# bue_steuerung_3.net
KiCad netlist of a schematic drawn in EAGLE
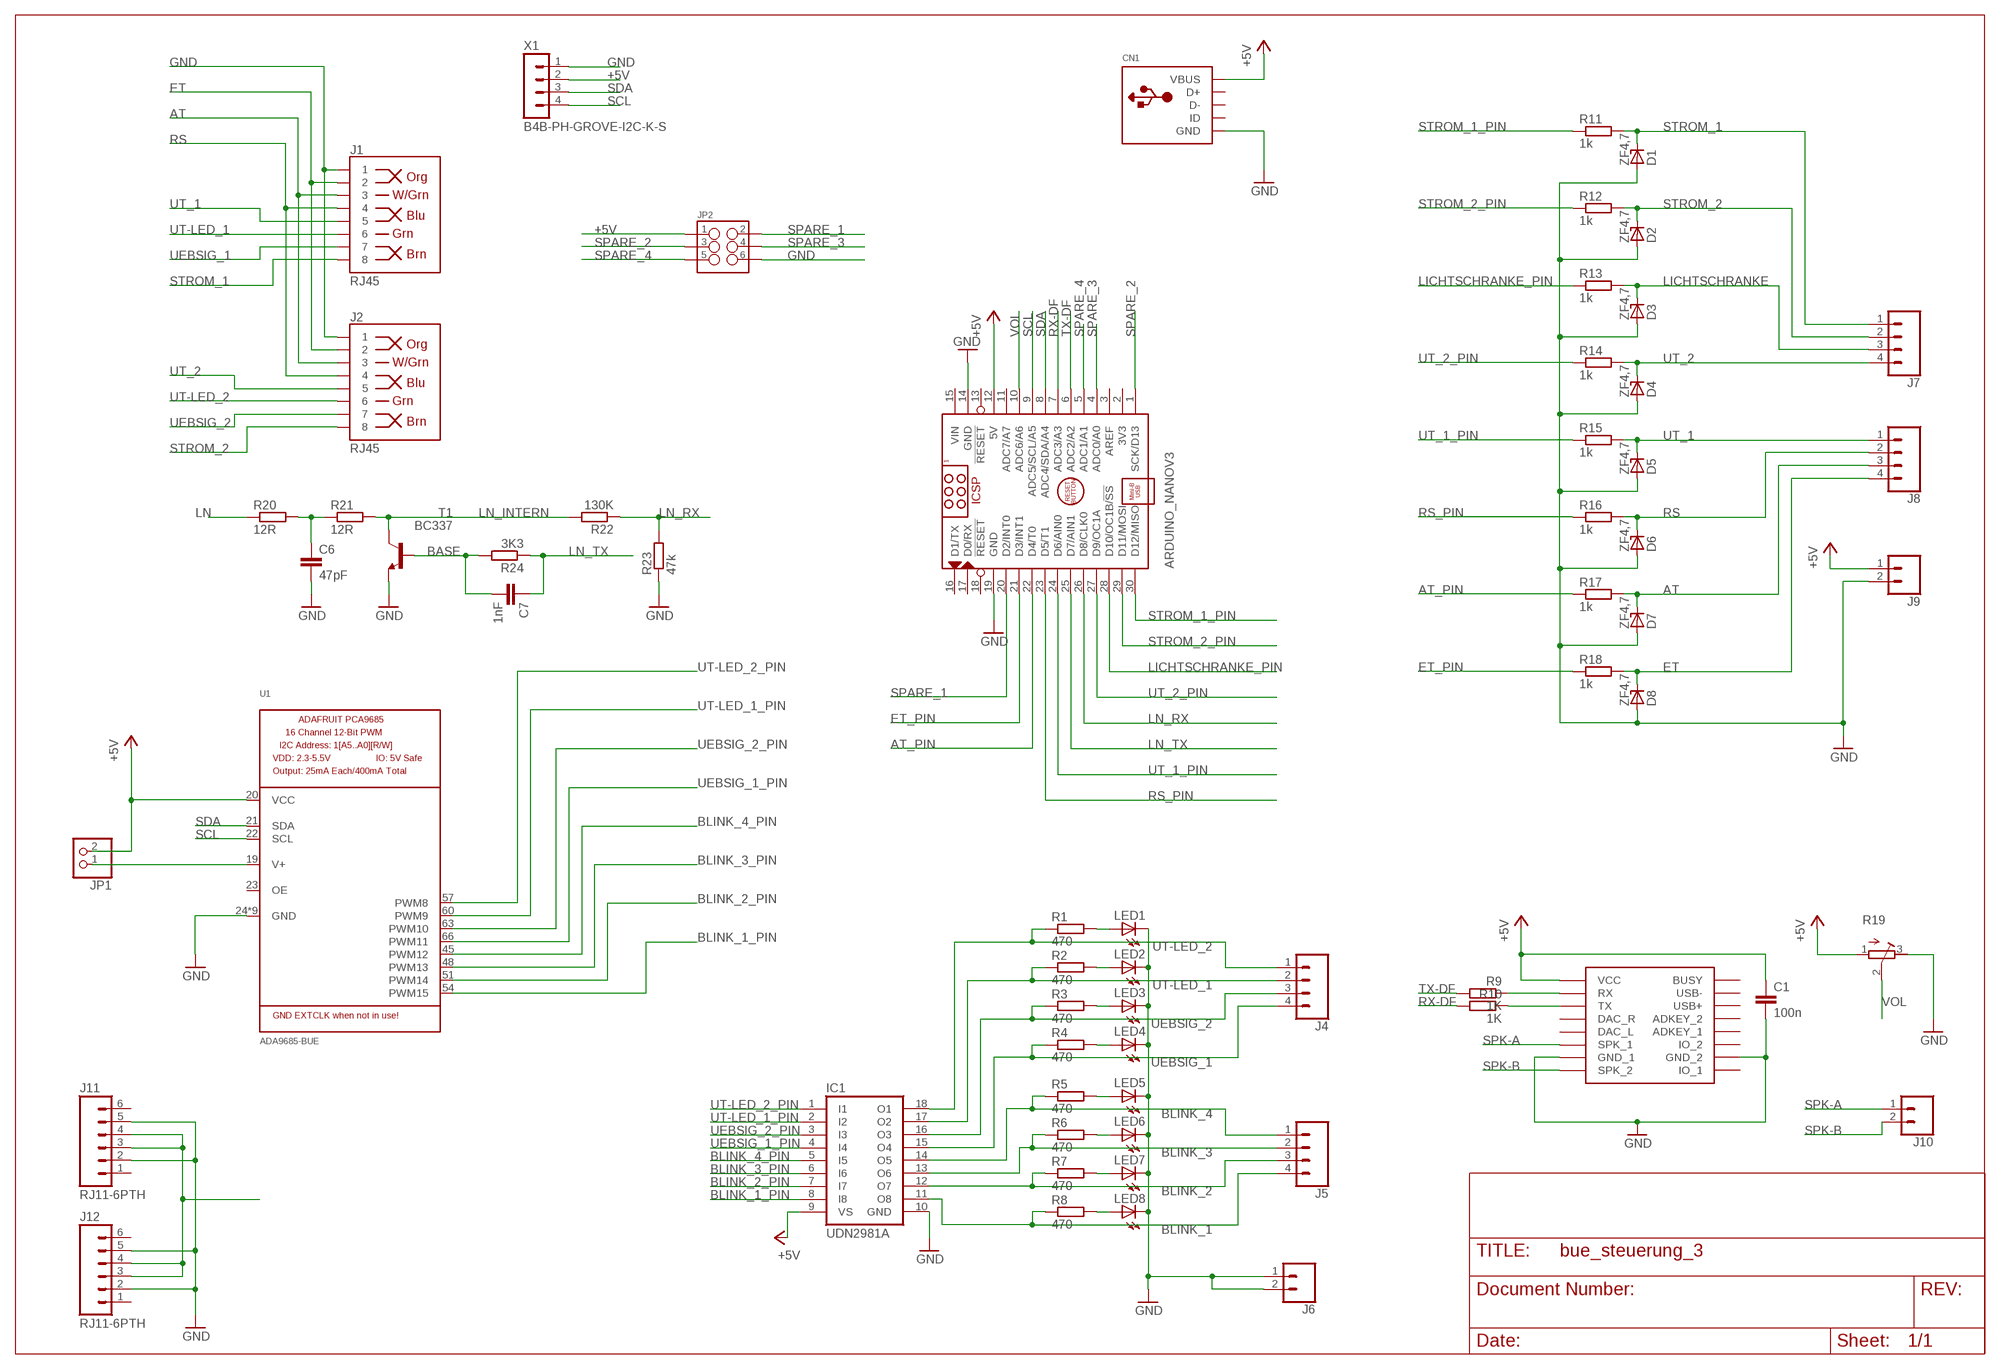
[diagram p0: schematic, sheet 1]

(export (version "E")
  (design (tool "Eeschema 10.0.6"))
  (components
    (comp (ref "ARDUINO_NANOV3")
      (value "ARDUINO_NANO")
      (footprint "eagle-import:ARDUINO_NANO")
      (libsource (lib "eagle-import") (part "ARDUINO_NANO"))
    )
    (comp (ref "C1")
      (value "100n")
      (footprint "eagle-import:C0805")
      (libsource (lib "eagle-import") (part "C-EUC0805"))
    )
    (comp (ref "C6")
      (value "47pF")
      (footprint "eagle-import:C025-024X044")
      (libsource (lib "eagle-import") (part "C-EU025-024X044"))
    )
    (comp (ref "C7")
      (value "1nF")
      (footprint "eagle-import:C025-025X050")
      (libsource (lib "eagle-import") (part "C-EU025-025X050"))
    )
    (comp (ref "CN1")
      (value "USBMOLEX")
      (footprint "eagle-import:USB-MINIB-THM-MOLEX")
      (libsource (lib "eagle-import") (part "USBMOLEX"))
    )
    (comp (ref "D1")
      (value "ZF4,7")
      (footprint "eagle-import:ZDIO-7.5")
      (libsource (lib "eagle-import") (part "ZENER-DIODEZD-7.5"))
    )
    (comp (ref "D2")
      (value "ZF4,7")
      (footprint "eagle-import:ZDIO-7.5")
      (libsource (lib "eagle-import") (part "ZENER-DIODEZD-7.5"))
    )
    (comp (ref "D3")
      (value "ZF4,7")
      (footprint "eagle-import:ZDIO-7.5")
      (libsource (lib "eagle-import") (part "ZENER-DIODEZD-7.5"))
    )
    (comp (ref "D4")
      (value "ZF4,7")
      (footprint "eagle-import:ZDIO-7.5")
      (libsource (lib "eagle-import") (part "ZENER-DIODEZD-7.5"))
    )
    (comp (ref "D5")
      (value "ZF4,7")
      (footprint "eagle-import:ZDIO-7.5")
      (libsource (lib "eagle-import") (part "ZENER-DIODEZD-7.5"))
    )
    (comp (ref "D6")
      (value "ZF4,7")
      (footprint "eagle-import:ZDIO-7.5")
      (libsource (lib "eagle-import") (part "ZENER-DIODEZD-7.5"))
    )
    (comp (ref "D7")
      (value "ZF4,7")
      (footprint "eagle-import:ZDIO-7.5")
      (libsource (lib "eagle-import") (part "ZENER-DIODEZD-7.5"))
    )
    (comp (ref "D8")
      (value "ZF4,7")
      (footprint "eagle-import:ZDIO-7.5")
      (libsource (lib "eagle-import") (part "ZENER-DIODEZD-7.5"))
    )
    (comp (ref "IC1")
      (value "UDN2981A")
      (footprint "eagle-import:DIL18")
      (libsource (lib "eagle-import") (part "UDN298A1"))
    )
    (comp (ref "J1")
      (value "RJ45")
      (footprint "eagle-import:RJ45-8")
      (libsource (lib "eagle-import") (part "RJ45-8"))
    )
    (comp (ref "J2")
      (value "RJ45")
      (footprint "eagle-import:RJ45-8")
      (libsource (lib "eagle-import") (part "RJ45-8"))
    )
    (comp (ref "J4")
      (value "CONN_04SCREW")
      (footprint "eagle-import:SCREWTERMINAL-3.5MM-4")
      (libsource (lib "eagle-import") (part "CONN_04SCREW"))
    )
    (comp (ref "J5")
      (value "CONN_04SCREW")
      (footprint "eagle-import:SCREWTERMINAL-3.5MM-4")
      (libsource (lib "eagle-import") (part "CONN_04SCREW"))
    )
    (comp (ref "J6")
      (value "CONN_023.5MM")
      (footprint "eagle-import:SCREWTERMINAL-3.5MM-2")
      (libsource (lib "eagle-import") (part "CONN_023.5MM"))
    )
    (comp (ref "J7")
      (value "CONN_04SCREW")
      (footprint "eagle-import:SCREWTERMINAL-3.5MM-4")
      (libsource (lib "eagle-import") (part "CONN_04SCREW"))
    )
    (comp (ref "J8")
      (value "CONN_04SCREW")
      (footprint "eagle-import:SCREWTERMINAL-3.5MM-4")
      (libsource (lib "eagle-import") (part "CONN_04SCREW"))
    )
    (comp (ref "J9")
      (value "CONN_023.5MM")
      (footprint "eagle-import:SCREWTERMINAL-3.5MM-2")
      (libsource (lib "eagle-import") (part "CONN_023.5MM"))
    )
    (comp (ref "J10")
      (value "CONN_023.5MM")
      (footprint "eagle-import:SCREWTERMINAL-3.5MM-2")
      (libsource (lib "eagle-import") (part "CONN_023.5MM"))
    )
    (comp (ref "J11")
      (value "RJ11-6PTH")
      (footprint "eagle-import:RJ11-6")
      (libsource (lib "eagle-import") (part "RJ11-6PTH"))
    )
    (comp (ref "J12")
      (value "RJ11-6PTH")
      (footprint "eagle-import:RJ11-6")
      (libsource (lib "eagle-import") (part "RJ11-6PTH"))
    )
    (comp (ref "JP1")
      (value "PINHD-1X2")
      (footprint "eagle-import:1X02")
      (libsource (lib "eagle-import") (part "PINHD-1X2"))
    )
    (comp (ref "JP2")
      (value "M03X2SHROUD")
      (footprint "eagle-import:2X3-SHROUDED")
      (libsource (lib "eagle-import") (part "M03X2SHROUD"))
    )
    (comp (ref "LED1")
      (value "LED3MM")
      (footprint "eagle-import:LED3MM")
      (libsource (lib "eagle-import") (part "LED3MM"))
    )
    (comp (ref "LED2")
      (value "LED3MM")
      (footprint "eagle-import:LED3MM")
      (libsource (lib "eagle-import") (part "LED3MM"))
    )
    (comp (ref "LED3")
      (value "LED3MM")
      (footprint "eagle-import:LED3MM")
      (libsource (lib "eagle-import") (part "LED3MM"))
    )
    (comp (ref "LED4")
      (value "LED3MM")
      (footprint "eagle-import:LED3MM")
      (libsource (lib "eagle-import") (part "LED3MM"))
    )
    (comp (ref "LED5")
      (value "LED3MM")
      (footprint "eagle-import:LED3MM")
      (libsource (lib "eagle-import") (part "LED3MM"))
    )
    (comp (ref "LED6")
      (value "LED3MM")
      (footprint "eagle-import:LED3MM")
      (libsource (lib "eagle-import") (part "LED3MM"))
    )
    (comp (ref "LED7")
      (value "LED3MM")
      (footprint "eagle-import:LED3MM")
      (libsource (lib "eagle-import") (part "LED3MM"))
    )
    (comp (ref "LED8")
      (value "LED3MM")
      (footprint "eagle-import:LED3MM")
      (libsource (lib "eagle-import") (part "LED3MM"))
    )
    (comp (ref "R1")
      (value "470")
      (footprint "eagle-import:0207_7")
      (libsource (lib "eagle-import") (part "resistor@1_R-EU_0207/7"))
    )
    (comp (ref "R2")
      (value "470")
      (footprint "eagle-import:0207_7")
      (libsource (lib "eagle-import") (part "resistor@1_R-EU_0207/7"))
    )
    (comp (ref "R3")
      (value "470")
      (footprint "eagle-import:0207_7")
      (libsource (lib "eagle-import") (part "resistor@1_R-EU_0207/7"))
    )
    (comp (ref "R4")
      (value "470")
      (footprint "eagle-import:0207_7")
      (libsource (lib "eagle-import") (part "resistor@1_R-EU_0207/7"))
    )
    (comp (ref "R5")
      (value "470")
      (footprint "eagle-import:0207_7")
      (libsource (lib "eagle-import") (part "resistor@1_R-EU_0207/7"))
    )
    (comp (ref "R6")
      (value "470")
      (footprint "eagle-import:0207_7")
      (libsource (lib "eagle-import") (part "resistor@1_R-EU_0207/7"))
    )
    (comp (ref "R7")
      (value "470")
      (footprint "eagle-import:0207_7")
      (libsource (lib "eagle-import") (part "resistor@1_R-EU_0207/7"))
    )
    (comp (ref "R8")
      (value "470")
      (footprint "eagle-import:0207_7")
      (libsource (lib "eagle-import") (part "resistor@1_R-EU_0207/7"))
    )
    (comp (ref "R9")
      (value "1K")
      (footprint "eagle-import:0207_7")
      (libsource (lib "eagle-import") (part "R-EU_0207/7"))
    )
    (comp (ref "R10")
      (value "1K")
      (footprint "eagle-import:0207_7")
      (libsource (lib "eagle-import") (part "R-EU_0207/7"))
    )
    (comp (ref "R11")
      (value "1k")
      (footprint "eagle-import:0207_7")
      (libsource (lib "eagle-import") (part "resistor@1_R-EU_0207/7"))
    )
    (comp (ref "R12")
      (value "1k")
      (footprint "eagle-import:0207_7")
      (libsource (lib "eagle-import") (part "resistor@1_R-EU_0207/7"))
    )
    (comp (ref "R13")
      (value "1k")
      (footprint "eagle-import:0207_7")
      (libsource (lib "eagle-import") (part "resistor@1_R-EU_0207/7"))
    )
    (comp (ref "R14")
      (value "1k")
      (footprint "eagle-import:0207_7")
      (libsource (lib "eagle-import") (part "resistor@1_R-EU_0207/7"))
    )
    (comp (ref "R15")
      (value "1k")
      (footprint "eagle-import:0207_7")
      (libsource (lib "eagle-import") (part "resistor@1_R-EU_0207/7"))
    )
    (comp (ref "R16")
      (value "1k")
      (footprint "eagle-import:0207_7")
      (libsource (lib "eagle-import") (part "resistor@1_R-EU_0207/7"))
    )
    (comp (ref "R17")
      (value "1k")
      (footprint "eagle-import:0207_7")
      (libsource (lib "eagle-import") (part "resistor@1_R-EU_0207/7"))
    )
    (comp (ref "R18")
      (value "1k")
      (footprint "eagle-import:0207_7")
      (libsource (lib "eagle-import") (part "resistor@1_R-EU_0207/7"))
    )
    (comp (ref "R19")
      (value "R-TRIMM64Y")
      (footprint "eagle-import:RTRIM64Y")
      (libsource (lib "eagle-import") (part "R-TRIMM64Y"))
    )
    (comp (ref "R20")
      (value "12R")
      (footprint "eagle-import:0207_7")
      (libsource (lib "eagle-import") (part "R-EU_0207/7"))
    )
    (comp (ref "R21")
      (value "12R")
      (footprint "eagle-import:0207_7")
      (libsource (lib "eagle-import") (part "R-EU_0207/7"))
    )
    (comp (ref "R22")
      (value "130K")
      (footprint "eagle-import:0207_7")
      (libsource (lib "eagle-import") (part "R-EU_0207/7"))
    )
    (comp (ref "R23")
      (value "47k")
      (footprint "eagle-import:0207_7")
      (libsource (lib "eagle-import") (part "R-EU_0207/7"))
    )
    (comp (ref "R24")
      (value "3K3")
      (footprint "eagle-import:0207_7")
      (libsource (lib "eagle-import") (part "R-EU_0207/7"))
    )
    (comp (ref "T1")
      (value "BC337")
      (footprint "eagle-import:TO92")
      (libsource (lib "eagle-import") (part "BC337"))
    )
    (comp (ref "U1")
      (value "ADA9685-BUE")
      (footprint "eagle-import:ADA9685-BUE")
      (libsource (lib "eagle-import") (part "ADA9685-BUE"))
    )
    (comp (ref "U2")
      (value "DFPLAYER")
      (footprint "eagle-import:DFPLAYER")
      (libsource (lib "eagle-import") (part "DFPLAYER"))
    )
    (comp (ref "X1")
      (value "B4B-PH-GROVE-I2C-K-S")
      (footprint "eagle-import:B4B-PH-K-S")
      (libsource (lib "eagle-import") (part "B4B-PH-GROVE-I2C-K-S"))
    )
  )
  (nets
    (net (code "1") (name "+5V") (class "Default")
      (node (ref "ARDUINO_NANOV3") (pin "12") (pinfunction "5V_12") (pintype "power_in"))
      (node (ref "C1") (pin "1") (pinfunction "1_1") (pintype "passive"))
      (node (ref "CN1") (pin "VBUS") (pinfunction "VBUS_VBUS") (pintype "power_in"))
      (node (ref "IC1") (pin "9") (pinfunction "VS_9") (pintype "passive"))
      (node (ref "J9") (pin "1") (pinfunction "1_1") (pintype "passive"))
      (node (ref "JP1") (pin "2") (pinfunction "2_2") (pintype "passive"))
      (node (ref "JP2") (pin "1") (pinfunction "1_1") (pintype "bidirectional"))
      (node (ref "R19") (pin "1") (pinfunction "A_1") (pintype "passive"))
      (node (ref "U1") (pin "20") (pinfunction "VCC_20") (pintype "power_in"))
      (node (ref "U2") (pin "VCC") (pinfunction "VCC_VCC") (pintype "bidirectional"))
      (node (ref "X1") (pin "2") (pinfunction "3_2") (pintype "passive"))
    )
    (net (code "2") (name "/AT") (class "Default")
      (node (ref "D7") (pin "C") (pinfunction "C_C") (pintype "passive"))
      (node (ref "J1") (pin "3") (pinfunction "3_3") (pintype "bidirectional"))
      (node (ref "J2") (pin "3") (pinfunction "3_3") (pintype "bidirectional"))
      (node (ref "J8") (pin "3") (pinfunction "3_3") (pintype "passive"))
      (node (ref "R17") (pin "2") (pinfunction "2_2") (pintype "passive"))
    )
    (net (code "3") (name "/AT_PIN") (class "Default")
      (node (ref "ARDUINO_NANOV3") (pin "22") (pinfunction "D4/T0_22") (pintype "bidirectional"))
      (node (ref "R17") (pin "1") (pinfunction "1_1") (pintype "passive"))
    )
    (net (code "4") (name "/BASE") (class "Default")
      (node (ref "C7") (pin "2") (pinfunction "2_2") (pintype "passive"))
      (node (ref "R24") (pin "2") (pinfunction "2_2") (pintype "passive"))
      (node (ref "T1") (pin "2") (pinfunction "B_2") (pintype "passive"))
    )
    (net (code "5") (name "/BLINK_1") (class "Default")
      (node (ref "IC1") (pin "11") (pinfunction "O8_11") (pintype "open_collector"))
      (node (ref "J5") (pin "4") (pinfunction "4_4") (pintype "passive"))
      (node (ref "R8") (pin "1") (pinfunction "1_1") (pintype "passive"))
    )
    (net (code "6") (name "/BLINK_1_PIN") (class "Default")
      (node (ref "IC1") (pin "8") (pinfunction "I8_8") (pintype "input"))
      (node (ref "U1") (pin "54") (pinfunction "PWM15_54") (pintype "output"))
    )
    (net (code "7") (name "/BLINK_2") (class "Default")
      (node (ref "IC1") (pin "12") (pinfunction "O7_12") (pintype "open_collector"))
      (node (ref "J5") (pin "3") (pinfunction "3_3") (pintype "passive"))
      (node (ref "R7") (pin "1") (pinfunction "1_1") (pintype "passive"))
    )
    (net (code "8") (name "/BLINK_2_PIN") (class "Default")
      (node (ref "IC1") (pin "7") (pinfunction "I7_7") (pintype "input"))
      (node (ref "U1") (pin "51") (pinfunction "PWM14_51") (pintype "output"))
    )
    (net (code "9") (name "/BLINK_3") (class "Default")
      (node (ref "IC1") (pin "13") (pinfunction "O6_13") (pintype "open_collector"))
      (node (ref "J5") (pin "2") (pinfunction "2_2") (pintype "passive"))
      (node (ref "R6") (pin "1") (pinfunction "1_1") (pintype "passive"))
    )
    (net (code "10") (name "/BLINK_3_PIN") (class "Default")
      (node (ref "IC1") (pin "6") (pinfunction "I6_6") (pintype "input"))
      (node (ref "U1") (pin "48") (pinfunction "PWM13_48") (pintype "output"))
    )
    (net (code "11") (name "/BLINK_4") (class "Default")
      (node (ref "IC1") (pin "14") (pinfunction "O5_14") (pintype "open_collector"))
      (node (ref "J5") (pin "1") (pinfunction "1_1") (pintype "passive"))
      (node (ref "R5") (pin "1") (pinfunction "1_1") (pintype "passive"))
    )
    (net (code "12") (name "/BLINK_4_PIN") (class "Default")
      (node (ref "IC1") (pin "5") (pinfunction "I5_5") (pintype "input"))
      (node (ref "U1") (pin "45") (pinfunction "PWM12_45") (pintype "output"))
    )
    (net (code "13") (name "/ET") (class "Default")
      (node (ref "D8") (pin "C") (pinfunction "C_C") (pintype "passive"))
      (node (ref "J1") (pin "2") (pinfunction "2_2") (pintype "bidirectional"))
      (node (ref "J2") (pin "2") (pinfunction "2_2") (pintype "bidirectional"))
      (node (ref "J8") (pin "4") (pinfunction "4_4") (pintype "passive"))
      (node (ref "R18") (pin "2") (pinfunction "2_2") (pintype "passive"))
    )
    (net (code "14") (name "/ET_PIN") (class "Default")
      (node (ref "ARDUINO_NANOV3") (pin "21") (pinfunction "D3/INT1_21") (pintype "bidirectional"))
      (node (ref "R18") (pin "1") (pinfunction "1_1") (pintype "passive"))
    )
    (net (code "15") (name "/LICHTSCHRANKE") (class "Default")
      (node (ref "D3") (pin "C") (pinfunction "C_C") (pintype "passive"))
      (node (ref "J7") (pin "3") (pinfunction "3_3") (pintype "passive"))
      (node (ref "R13") (pin "2") (pinfunction "2_2") (pintype "passive"))
    )
    (net (code "16") (name "/LICHTSCHRANKE_PIN") (class "Default")
      (node (ref "ARDUINO_NANOV3") (pin "28") (pinfunction "D10/OC1B/~{SS}_28") (pintype "bidirectional"))
      (node (ref "R13") (pin "1") (pinfunction "1_1") (pintype "passive"))
    )
    (net (code "17") (name "/LN") (class "Default")
      (node (ref "J11") (pin "3") (pinfunction "3_3") (pintype "passive"))
      (node (ref "J11") (pin "4") (pinfunction "4_4") (pintype "passive"))
      (node (ref "J12") (pin "3") (pinfunction "3_3") (pintype "passive"))
      (node (ref "J12") (pin "4") (pinfunction "4_4") (pintype "passive"))
      (node (ref "R20") (pin "1") (pinfunction "1_1") (pintype "passive"))
    )
    (net (code "18") (name "/LN_INTERN") (class "Default")
      (node (ref "R21") (pin "2") (pinfunction "2_2") (pintype "passive"))
      (node (ref "R22") (pin "2") (pinfunction "2_2") (pintype "passive"))
      (node (ref "T1") (pin "3") (pinfunction "C_3") (pintype "passive"))
    )
    (net (code "19") (name "/LN_RX") (class "Default")
      (node (ref "ARDUINO_NANOV3") (pin "26") (pinfunction "D8/CLK0_26") (pintype "bidirectional"))
      (node (ref "R22") (pin "1") (pinfunction "1_1") (pintype "passive"))
      (node (ref "R23") (pin "2") (pinfunction "2_2") (pintype "passive"))
    )
    (net (code "20") (name "/LN_TX") (class "Default")
      (node (ref "ARDUINO_NANOV3") (pin "25") (pinfunction "D7/AIN1_25") (pintype "bidirectional"))
      (node (ref "C7") (pin "1") (pinfunction "1_1") (pintype "passive"))
      (node (ref "R24") (pin "1") (pinfunction "1_1") (pintype "passive"))
    )
    (net (code "21") (name "/RS") (class "Default")
      (node (ref "D6") (pin "C") (pinfunction "C_C") (pintype "passive"))
      (node (ref "J1") (pin "4") (pinfunction "4_4") (pintype "bidirectional"))
      (node (ref "J2") (pin "4") (pinfunction "4_4") (pintype "bidirectional"))
      (node (ref "J8") (pin "2") (pinfunction "2_2") (pintype "passive"))
      (node (ref "R16") (pin "2") (pinfunction "2_2") (pintype "passive"))
    )
    (net (code "22") (name "/RS_PIN") (class "Default")
      (node (ref "ARDUINO_NANOV3") (pin "23") (pinfunction "D5/T1_23") (pintype "bidirectional"))
      (node (ref "R16") (pin "1") (pinfunction "1_1") (pintype "passive"))
    )
    (net (code "23") (name "/RX-DF") (class "Default")
      (node (ref "ARDUINO_NANOV3") (pin "7") (pinfunction "ADC3/A3_7") (pintype "bidirectional"))
      (node (ref "R10") (pin "2") (pinfunction "2_2") (pintype "passive"))
    )
    (net (code "24") (name "/SCL") (class "Default")
      (node (ref "ARDUINO_NANOV3") (pin "9") (pinfunction "ADC5/SCL/A5_9") (pintype "bidirectional"))
      (node (ref "U1") (pin "22") (pinfunction "SCL_22") (pintype "bidirectional"))
      (node (ref "X1") (pin "4") (pinfunction "1_4") (pintype "passive"))
    )
    (net (code "25") (name "/SDA") (class "Default")
      (node (ref "ARDUINO_NANOV3") (pin "8") (pinfunction "ADC4/SDA/A4_8") (pintype "bidirectional"))
      (node (ref "U1") (pin "21") (pinfunction "SDA_21") (pintype "bidirectional"))
      (node (ref "X1") (pin "3") (pinfunction "2_3") (pintype "passive"))
    )
    (net (code "26") (name "/SPARE_1") (class "Default")
      (node (ref "ARDUINO_NANOV3") (pin "20") (pinfunction "D2/INT0_20") (pintype "bidirectional"))
      (node (ref "JP2") (pin "2") (pinfunction "2_2") (pintype "bidirectional"))
    )
    (net (code "27") (name "/SPARE_2") (class "Default")
      (node (ref "ARDUINO_NANOV3") (pin "1") (pinfunction "SCK/D13_1") (pintype "bidirectional"))
      (node (ref "JP2") (pin "3") (pinfunction "3_3") (pintype "bidirectional"))
    )
    (net (code "28") (name "/SPARE_3") (class "Default")
      (node (ref "ARDUINO_NANOV3") (pin "4") (pinfunction "ADC0/A0_4") (pintype "bidirectional"))
      (node (ref "JP2") (pin "4") (pinfunction "4_4") (pintype "bidirectional"))
    )
    (net (code "29") (name "/SPARE_4") (class "Default")
      (node (ref "ARDUINO_NANOV3") (pin "5") (pinfunction "ADC1/A1_5") (pintype "bidirectional"))
      (node (ref "JP2") (pin "5") (pinfunction "5_5") (pintype "bidirectional"))
    )
    (net (code "30") (name "/SPK-A") (class "Default")
      (node (ref "J10") (pin "1") (pinfunction "1_1") (pintype "passive"))
      (node (ref "U2") (pin "SPK1") (pinfunction "SPK_1_SPK1") (pintype "bidirectional"))
    )
    (net (code "31") (name "/SPK-B") (class "Default")
      (node (ref "J10") (pin "2") (pinfunction "2_2") (pintype "passive"))
      (node (ref "U2") (pin "SPK2") (pinfunction "SPK_2_SPK2") (pintype "bidirectional"))
    )
    (net (code "32") (name "/STROM_1") (class "Default")
      (node (ref "D1") (pin "C") (pinfunction "C_C") (pintype "passive"))
      (node (ref "J1") (pin "8") (pinfunction "8_8") (pintype "bidirectional"))
      (node (ref "J7") (pin "1") (pinfunction "1_1") (pintype "passive"))
      (node (ref "R11") (pin "2") (pinfunction "2_2") (pintype "passive"))
    )
    (net (code "33") (name "/STROM_1_PIN") (class "Default")
      (node (ref "ARDUINO_NANOV3") (pin "30") (pinfunction "D12/MISO_30") (pintype "bidirectional"))
      (node (ref "R11") (pin "1") (pinfunction "1_1") (pintype "passive"))
    )
    (net (code "34") (name "/STROM_2") (class "Default")
      (node (ref "D2") (pin "C") (pinfunction "C_C") (pintype "passive"))
      (node (ref "J2") (pin "8") (pinfunction "8_8") (pintype "bidirectional"))
      (node (ref "J7") (pin "2") (pinfunction "2_2") (pintype "passive"))
      (node (ref "R12") (pin "2") (pinfunction "2_2") (pintype "passive"))
    )
    (net (code "35") (name "/STROM_2_PIN") (class "Default")
      (node (ref "ARDUINO_NANOV3") (pin "29") (pinfunction "D11/MOSI_29") (pintype "bidirectional"))
      (node (ref "R12") (pin "1") (pinfunction "1_1") (pintype "passive"))
    )
    (net (code "36") (name "/TX-DF") (class "Default")
      (node (ref "ARDUINO_NANOV3") (pin "6") (pinfunction "ADC2/A2_6") (pintype "bidirectional"))
      (node (ref "R9") (pin "2") (pinfunction "2_2") (pintype "passive"))
    )
    (net (code "37") (name "/UEBSIG_1") (class "Default")
      (node (ref "IC1") (pin "15") (pinfunction "O4_15") (pintype "open_collector"))
      (node (ref "J1") (pin "7") (pinfunction "7_7") (pintype "bidirectional"))
      (node (ref "J4") (pin "4") (pinfunction "4_4") (pintype "passive"))
      (node (ref "R4") (pin "1") (pinfunction "1_1") (pintype "passive"))
    )
    (net (code "38") (name "/UEBSIG_1_PIN") (class "Default")
      (node (ref "IC1") (pin "4") (pinfunction "I4_4") (pintype "input"))
      (node (ref "U1") (pin "66") (pinfunction "PWM11_66") (pintype "output"))
    )
    (net (code "39") (name "/UEBSIG_2") (class "Default")
      (node (ref "IC1") (pin "16") (pinfunction "O3_16") (pintype "open_collector"))
      (node (ref "J2") (pin "7") (pinfunction "7_7") (pintype "bidirectional"))
      (node (ref "J4") (pin "3") (pinfunction "3_3") (pintype "passive"))
      (node (ref "R3") (pin "1") (pinfunction "1_1") (pintype "passive"))
    )
    (net (code "40") (name "/UEBSIG_2_PIN") (class "Default")
      (node (ref "IC1") (pin "3") (pinfunction "I3_3") (pintype "input"))
      (node (ref "U1") (pin "63") (pinfunction "PWM10_63") (pintype "output"))
    )
    (net (code "41") (name "/UT-LED_1") (class "Default")
      (node (ref "IC1") (pin "17") (pinfunction "O2_17") (pintype "open_collector"))
      (node (ref "J1") (pin "6") (pinfunction "6_6") (pintype "bidirectional"))
      (node (ref "J4") (pin "2") (pinfunction "2_2") (pintype "passive"))
      (node (ref "R2") (pin "1") (pinfunction "1_1") (pintype "passive"))
    )
    (net (code "42") (name "/UT-LED_1_PIN") (class "Default")
      (node (ref "IC1") (pin "2") (pinfunction "I2_2") (pintype "input"))
      (node (ref "U1") (pin "60") (pinfunction "PWM9_60") (pintype "output"))
    )
    (net (code "43") (name "/UT-LED_2") (class "Default")
      (node (ref "IC1") (pin "18") (pinfunction "O1_18") (pintype "open_collector"))
      (node (ref "J2") (pin "6") (pinfunction "6_6") (pintype "bidirectional"))
      (node (ref "J4") (pin "1") (pinfunction "1_1") (pintype "passive"))
      (node (ref "R1") (pin "1") (pinfunction "1_1") (pintype "passive"))
    )
    (net (code "44") (name "/UT-LED_2_PIN") (class "Default")
      (node (ref "IC1") (pin "1") (pinfunction "I1_1") (pintype "input"))
      (node (ref "U1") (pin "57") (pinfunction "PWM8_57") (pintype "output"))
    )
    (net (code "45") (name "/UT_1") (class "Default")
      (node (ref "D5") (pin "C") (pinfunction "C_C") (pintype "passive"))
      (node (ref "J1") (pin "5") (pinfunction "5_5") (pintype "bidirectional"))
      (node (ref "J8") (pin "1") (pinfunction "1_1") (pintype "passive"))
      (node (ref "R15") (pin "2") (pinfunction "2_2") (pintype "passive"))
    )
    (net (code "46") (name "/UT_1_PIN") (class "Default")
      (node (ref "ARDUINO_NANOV3") (pin "24") (pinfunction "D6/AIN0_24") (pintype "bidirectional"))
      (node (ref "R15") (pin "1") (pinfunction "1_1") (pintype "passive"))
    )
    (net (code "47") (name "/UT_2") (class "Default")
      (node (ref "D4") (pin "C") (pinfunction "C_C") (pintype "passive"))
      (node (ref "J2") (pin "5") (pinfunction "5_5") (pintype "bidirectional"))
      (node (ref "J7") (pin "4") (pinfunction "4_4") (pintype "passive"))
      (node (ref "R14") (pin "2") (pinfunction "2_2") (pintype "passive"))
    )
    (net (code "48") (name "/UT_2_PIN") (class "Default")
      (node (ref "ARDUINO_NANOV3") (pin "27") (pinfunction "D9/OC1A_27") (pintype "bidirectional"))
      (node (ref "R14") (pin "1") (pinfunction "1_1") (pintype "passive"))
    )
    (net (code "49") (name "/VIN") (class "Default")
      (node (ref "ARDUINO_NANOV3") (pin "15") (pinfunction "VIN_15") (pintype "power_in"))
    )
    (net (code "50") (name "/VOL") (class "Default")
      (node (ref "ARDUINO_NANOV3") (pin "10") (pinfunction "ADC6/A6_10") (pintype "bidirectional"))
      (node (ref "R19") (pin "2") (pinfunction "S_2") (pintype "passive"))
    )
    (net (code "51") (name "GND") (class "Default")
      (node (ref "ARDUINO_NANOV3") (pin "14") (pinfunction "GND_14") (pintype "power_in"))
      (node (ref "ARDUINO_NANOV3") (pin "19") (pinfunction "GND_19") (pintype "power_in"))
      (node (ref "C1") (pin "2") (pinfunction "2_2") (pintype "passive"))
      (node (ref "C6") (pin "2") (pinfunction "2_2") (pintype "passive"))
      (node (ref "CN1") (pin "GND") (pinfunction "GND_GND") (pintype "power_in"))
      (node (ref "D1") (pin "A") (pinfunction "A_A") (pintype "passive"))
      (node (ref "D2") (pin "A") (pinfunction "A_A") (pintype "passive"))
      (node (ref "D3") (pin "A") (pinfunction "A_A") (pintype "passive"))
      (node (ref "D4") (pin "A") (pinfunction "A_A") (pintype "passive"))
      (node (ref "D5") (pin "A") (pinfunction "A_A") (pintype "passive"))
      (node (ref "D6") (pin "A") (pinfunction "A_A") (pintype "passive"))
      (node (ref "D7") (pin "A") (pinfunction "A_A") (pintype "passive"))
      (node (ref "D8") (pin "A") (pinfunction "A_A") (pintype "passive"))
      (node (ref "IC1") (pin "10") (pinfunction "GND_10") (pintype "power_in"))
      (node (ref "J1") (pin "1") (pinfunction "1_1") (pintype "bidirectional"))
      (node (ref "J11") (pin "2") (pinfunction "2_2") (pintype "passive"))
      (node (ref "J11") (pin "5") (pinfunction "5_5") (pintype "passive"))
      (node (ref "J12") (pin "2") (pinfunction "2_2") (pintype "passive"))
      (node (ref "J12") (pin "5") (pinfunction "5_5") (pintype "passive"))
      (node (ref "J2") (pin "1") (pinfunction "1_1") (pintype "bidirectional"))
      (node (ref "J6") (pin "1") (pinfunction "1_1") (pintype "passive"))
      (node (ref "J6") (pin "2") (pinfunction "2_2") (pintype "passive"))
      (node (ref "J9") (pin "2") (pinfunction "2_2") (pintype "passive"))
      (node (ref "JP2") (pin "6") (pinfunction "6_6") (pintype "bidirectional"))
      (node (ref "LED1") (pin "K") (pinfunction "C_K") (pintype "passive"))
      (node (ref "LED2") (pin "K") (pinfunction "C_K") (pintype "passive"))
      (node (ref "LED3") (pin "K") (pinfunction "C_K") (pintype "passive"))
      (node (ref "LED4") (pin "K") (pinfunction "C_K") (pintype "passive"))
      (node (ref "LED5") (pin "K") (pinfunction "C_K") (pintype "passive"))
      (node (ref "LED6") (pin "K") (pinfunction "C_K") (pintype "passive"))
      (node (ref "LED7") (pin "K") (pinfunction "C_K") (pintype "passive"))
      (node (ref "LED8") (pin "K") (pinfunction "C_K") (pintype "passive"))
      (node (ref "R19") (pin "3") (pinfunction "E_3") (pintype "passive"))
      (node (ref "R23") (pin "1") (pinfunction "1_1") (pintype "passive"))
      (node (ref "T1") (pin "1") (pinfunction "E_1") (pintype "passive"))
      (node (ref "U1") (pin "24") (pinfunction "GND_24") (pintype "power_in"))
      (node (ref "U1") (pin "43") (pinfunction "GND_43") (pintype "power_in"))
      (node (ref "U1") (pin "46") (pinfunction "GND_46") (pintype "power_in"))
      (node (ref "U1") (pin "49") (pinfunction "GND_49") (pintype "power_in"))
      (node (ref "U1") (pin "52") (pinfunction "GND_52") (pintype "power_in"))
      (node (ref "U1") (pin "55") (pinfunction "GND_55") (pintype "power_in"))
      (node (ref "U1") (pin "58") (pinfunction "GND_58") (pintype "power_in"))
      (node (ref "U1") (pin "61") (pinfunction "GND_61") (pintype "power_in"))
      (node (ref "U1") (pin "64") (pinfunction "GND_64") (pintype "power_in"))
      (node (ref "U2") (pin "GND_1") (pinfunction "GND_1_GND_1") (pintype "bidirectional"))
      (node (ref "U2") (pin "GND_2") (pinfunction "GND_2_GND_2") (pintype "bidirectional"))
      (node (ref "X1") (pin "1") (pinfunction "4_1") (pintype "passive"))
    )
    (net (code "52") (name "Net-(C6-Pad1)") (class "Default")
      (node (ref "C6") (pin "1") (pinfunction "1_1") (pintype "passive"))
      (node (ref "R20") (pin "2") (pinfunction "2_2") (pintype "passive"))
      (node (ref "R21") (pin "1") (pinfunction "1_1") (pintype "passive"))
    )
    (net (code "53") (name "Net-(LED1-PadA)") (class "Default")
      (node (ref "LED1") (pin "A") (pinfunction "A_A") (pintype "passive"))
      (node (ref "R1") (pin "2") (pinfunction "2_2") (pintype "passive"))
    )
    (net (code "54") (name "Net-(LED2-PadA)") (class "Default")
      (node (ref "LED2") (pin "A") (pinfunction "A_A") (pintype "passive"))
      (node (ref "R2") (pin "2") (pinfunction "2_2") (pintype "passive"))
    )
    (net (code "55") (name "Net-(LED3-PadA)") (class "Default")
      (node (ref "LED3") (pin "A") (pinfunction "A_A") (pintype "passive"))
      (node (ref "R3") (pin "2") (pinfunction "2_2") (pintype "passive"))
    )
    (net (code "56") (name "Net-(LED4-PadA)") (class "Default")
      (node (ref "LED4") (pin "A") (pinfunction "A_A") (pintype "passive"))
      (node (ref "R4") (pin "2") (pinfunction "2_2") (pintype "passive"))
    )
    (net (code "57") (name "Net-(LED5-PadA)") (class "Default")
      (node (ref "LED5") (pin "A") (pinfunction "A_A") (pintype "passive"))
      (node (ref "R5") (pin "2") (pinfunction "2_2") (pintype "passive"))
    )
    (net (code "58") (name "Net-(LED6-PadA)") (class "Default")
      (node (ref "LED6") (pin "A") (pinfunction "A_A") (pintype "passive"))
      (node (ref "R6") (pin "2") (pinfunction "2_2") (pintype "passive"))
    )
    (net (code "59") (name "Net-(LED7-PadA)") (class "Default")
      (node (ref "LED7") (pin "A") (pinfunction "A_A") (pintype "passive"))
      (node (ref "R7") (pin "2") (pinfunction "2_2") (pintype "passive"))
    )
    (net (code "60") (name "Net-(LED8-PadA)") (class "Default")
      (node (ref "LED8") (pin "A") (pinfunction "A_A") (pintype "passive"))
      (node (ref "R8") (pin "2") (pinfunction "2_2") (pintype "passive"))
    )
    (net (code "61") (name "Net-(R9-Pad1)") (class "Default")
      (node (ref "R9") (pin "1") (pinfunction "1_1") (pintype "passive"))
      (node (ref "U2") (pin "RX") (pinfunction "RX_RX") (pintype "bidirectional"))
    )
    (net (code "62") (name "Net-(R10-Pad1)") (class "Default")
      (node (ref "R10") (pin "1") (pinfunction "1_1") (pintype "passive"))
      (node (ref "U2") (pin "TX") (pinfunction "TX_TX") (pintype "bidirectional"))
    )
    (net (code "63") (name "Net-(U1-V+)") (class "Default")
      (node (ref "JP1") (pin "1") (pinfunction "1_1") (pintype "passive"))
      (node (ref "U1") (pin "19") (pinfunction "V+_19") (pintype "input"))
    )
    (net (code "64") (name "unconnected-(ARDUINO_NANOV3-3V3-Pad2)") (class "Default")
      (node (ref "ARDUINO_NANOV3") (pin "2") (pinfunction "3V3_2") (pintype "output"))
    )
    (net (code "65") (name "unconnected-(ARDUINO_NANOV3-ADC7{slash}A7-Pad11)") (class "Default")
      (node (ref "ARDUINO_NANOV3") (pin "11") (pinfunction "ADC7/A7_11") (pintype "bidirectional"))
    )
    (net (code "66") (name "unconnected-(ARDUINO_NANOV3-AREF-Pad3)") (class "Default")
      (node (ref "ARDUINO_NANOV3") (pin "3") (pinfunction "AREF_3") (pintype "input"))
    )
    (net (code "67") (name "unconnected-(ARDUINO_NANOV3-D0{slash}RX-Pad17)") (class "Default")
      (node (ref "ARDUINO_NANOV3") (pin "17") (pinfunction "D0/RX_17") (pintype "bidirectional"))
    )
    (net (code "68") (name "unconnected-(ARDUINO_NANOV3-D1{slash}TX-Pad16)") (class "Default")
      (node (ref "ARDUINO_NANOV3") (pin "16") (pinfunction "D1/TX_16") (pintype "bidirectional"))
    )
    (net (code "69") (name "unconnected-(ARDUINO_NANOV3-~{RESET}-Pad13)") (class "Default")
      (node (ref "ARDUINO_NANOV3") (pin "13") (pinfunction "~{RESET}_13") (pintype "input"))
    )
    (net (code "70") (name "unconnected-(ARDUINO_NANOV3-~{RESET}-Pad18)") (class "Default")
      (node (ref "ARDUINO_NANOV3") (pin "18") (pinfunction "~{RESET}_18") (pintype "input"))
    )
    (net (code "71") (name "unconnected-(CN1-PadD+)") (class "Default")
      (node (ref "CN1") (pin "D+") (pinfunction "D+_D+") (pintype "bidirectional"))
    )
    (net (code "72") (name "unconnected-(CN1-PadD-)") (class "Default")
      (node (ref "CN1") (pin "D-") (pinfunction "D-_D-") (pintype "bidirectional"))
    )
    (net (code "73") (name "unconnected-(CN1-PadID)") (class "Default")
      (node (ref "CN1") (pin "ID") (pinfunction "ID_ID") (pintype "bidirectional"))
    )
    (net (code "74") (name "unconnected-(J11-Pad1)") (class "Default")
      (node (ref "J11") (pin "1") (pinfunction "1_1") (pintype "passive"))
    )
    (net (code "75") (name "unconnected-(J11-Pad6)") (class "Default")
      (node (ref "J11") (pin "6") (pinfunction "6_6") (pintype "passive"))
    )
    (net (code "76") (name "unconnected-(J12-Pad1)") (class "Default")
      (node (ref "J12") (pin "1") (pinfunction "1_1") (pintype "passive"))
    )
    (net (code "77") (name "unconnected-(J12-Pad6)") (class "Default")
      (node (ref "J12") (pin "6") (pinfunction "6_6") (pintype "passive"))
    )
    (net (code "78") (name "unconnected-(U1-OE-Pad23)") (class "Default")
      (node (ref "U1") (pin "23") (pinfunction "OE_23") (pintype "input"))
    )
    (net (code "79") (name "unconnected-(U2-ADKEY_1-PadADKEY1)") (class "Default")
      (node (ref "U2") (pin "ADKEY1") (pinfunction "ADKEY_1_ADKEY1") (pintype "bidirectional"))
    )
    (net (code "80") (name "unconnected-(U2-ADKEY_2-PadADKEY2)") (class "Default")
      (node (ref "U2") (pin "ADKEY2") (pinfunction "ADKEY_2_ADKEY2") (pintype "bidirectional"))
    )
    (net (code "81") (name "unconnected-(U2-IO_1-PadIO1)") (class "Default")
      (node (ref "U2") (pin "IO1") (pinfunction "IO_1_IO1") (pintype "bidirectional"))
    )
    (net (code "82") (name "unconnected-(U2-IO_2-PadIO2)") (class "Default")
      (node (ref "U2") (pin "IO2") (pinfunction "IO_2_IO2") (pintype "bidirectional"))
    )
    (net (code "83") (name "unconnected-(U2-PadBUSY)") (class "Default")
      (node (ref "U2") (pin "BUSY") (pinfunction "BUSY_BUSY") (pintype "bidirectional"))
    )
    (net (code "84") (name "unconnected-(U2-PadDAC_L)") (class "Default")
      (node (ref "U2") (pin "DAC_L") (pinfunction "DAC_L_DAC_L") (pintype "bidirectional"))
    )
    (net (code "85") (name "unconnected-(U2-PadDAC_R)") (class "Default")
      (node (ref "U2") (pin "DAC_R") (pinfunction "DAC_R_DAC_R") (pintype "bidirectional"))
    )
    (net (code "86") (name "unconnected-(U2-PadUSB+)") (class "Default")
      (node (ref "U2") (pin "USB+") (pinfunction "USB+_USB+") (pintype "bidirectional"))
    )
    (net (code "87") (name "unconnected-(U2-PadUSB-)") (class "Default")
      (node (ref "U2") (pin "USB-") (pinfunction "USB-_USB-") (pintype "bidirectional"))
    )
  )
)
